# rtc.net
KiCad netlist of a schematic drawn in Altium Designer
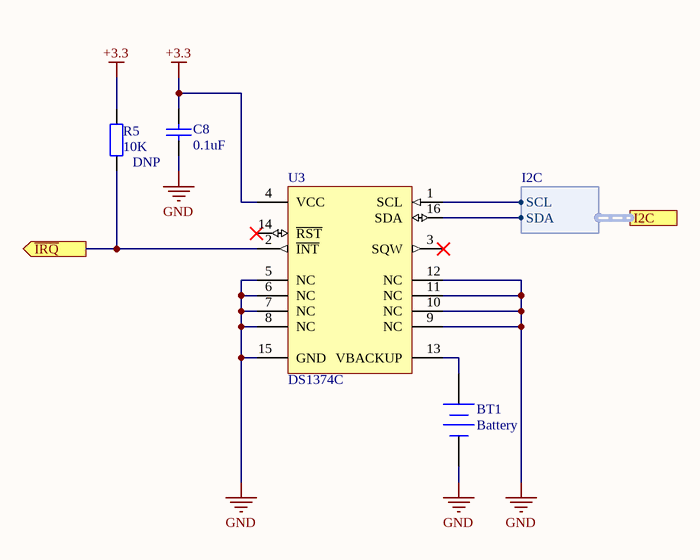
[diagram p0: rtc.SchDoc]

(export (version "E")
  (design (tool "Eeschema 10.0.6"))
  (components
    (comp (ref "BT1")
      (value "Battery")
      (footprint "3002")
      (description "Multicell Battery")
      (fields (field (name "PUBLISHER") "Altium Limited"))
      (libsource (lib "Miscellaneous Devices") (part "Battery"))
    )
    (comp (ref "C8")
      (value "0.1uF")
      (footprint "C0603")
      (description "Capacitor")
      (fields (field (name "Comment") "Cap"))
      (libsource (lib "Miscellaneous Devices") (part "Cap"))
    )
    (comp (ref "R5")
      (value "10K")
      (footprint "R0603")
      (description "Resistor")
      (fields (field (name "PLACE") "DNP") (field (name "Comment") "Res"))
      (libsource (lib "Miscellaneous Devices") (part "Res2"))
    )
    (comp (ref "U3")
      (value "DS1374C")
      (footprint "DS1374C")
      (description "DS1374 I2C, 32-Bit Binary Counter Watchdog RTC with Trickle Charger and Reset Input/Output")
      (libsource (lib "DS1374C") (part "DS1374C"))
    )
  )
  (nets
    (net (code "2") (name "+3.3") (class "Default")
      (node (ref "C8") (pin "1") (pinfunction "1_1") (pintype "passive"))
      (node (ref "R5") (pin "1") (pinfunction "1_1") (pintype "passive"))
      (node (ref "U3") (pin "4") (pinfunction "VCC_4") (pintype "power_in"))
    )
    (net (code "3") (name "/SCL") (class "Default")
      (node (ref "U3") (pin "1") (pinfunction "SCL_1") (pintype "input"))
    )
    (net (code "4") (name "/SDA") (class "Default")
      (node (ref "U3") (pin "16") (pinfunction "SDA_16") (pintype "bidirectional"))
    )
    (net (code "6") (name "/~{IRQ}") (class "Default")
      (node (ref "R5") (pin "2") (pinfunction "2_2") (pintype "passive"))
      (node (ref "U3") (pin "2") (pinfunction "~{INT}_2") (pintype "output"))
    )
    (net (code "7") (name "GND") (class "Default")
      (node (ref "BT1") (pin "2") (pinfunction "-_2") (pintype "passive"))
      (node (ref "C8") (pin "2") (pinfunction "2_2") (pintype "passive"))
      (node (ref "U3") (pin "10") (pinfunction "NC_10") (pintype "passive"))
      (node (ref "U3") (pin "11") (pinfunction "NC_11") (pintype "passive"))
      (node (ref "U3") (pin "12") (pinfunction "NC_12") (pintype "passive"))
      (node (ref "U3") (pin "15") (pinfunction "GND_15") (pintype "power_in"))
      (node (ref "U3") (pin "5") (pinfunction "NC_5") (pintype "passive"))
      (node (ref "U3") (pin "6") (pinfunction "NC_6") (pintype "passive"))
      (node (ref "U3") (pin "7") (pinfunction "NC_7") (pintype "passive"))
      (node (ref "U3") (pin "8") (pinfunction "NC_8") (pintype "passive"))
      (node (ref "U3") (pin "9") (pinfunction "NC_9") (pintype "passive"))
    )
    (net (code "8") (name "Net-(BT1-+)") (class "Default")
      (node (ref "BT1") (pin "1") (pinfunction "+_1") (pintype "passive"))
      (node (ref "U3") (pin "13") (pinfunction "VBACKUP_13") (pintype "power_in"))
    )
    (net (code "9") (name "unconnected-(U3-SQW-Pad3)") (class "Default")
      (node (ref "U3") (pin "3") (pinfunction "SQW_3") (pintype "output+no_connect"))
    )
    (net (code "10") (name "unconnected-(U3-~{RST}-Pad14)") (class "Default")
      (node (ref "U3") (pin "14") (pinfunction "~{RST}_14") (pintype "bidirectional+no_connect"))
    )
  )
)
